# Qwiic_PHT_Sensor_-_MS8607.net
KiCad netlist of a schematic drawn in EAGLE
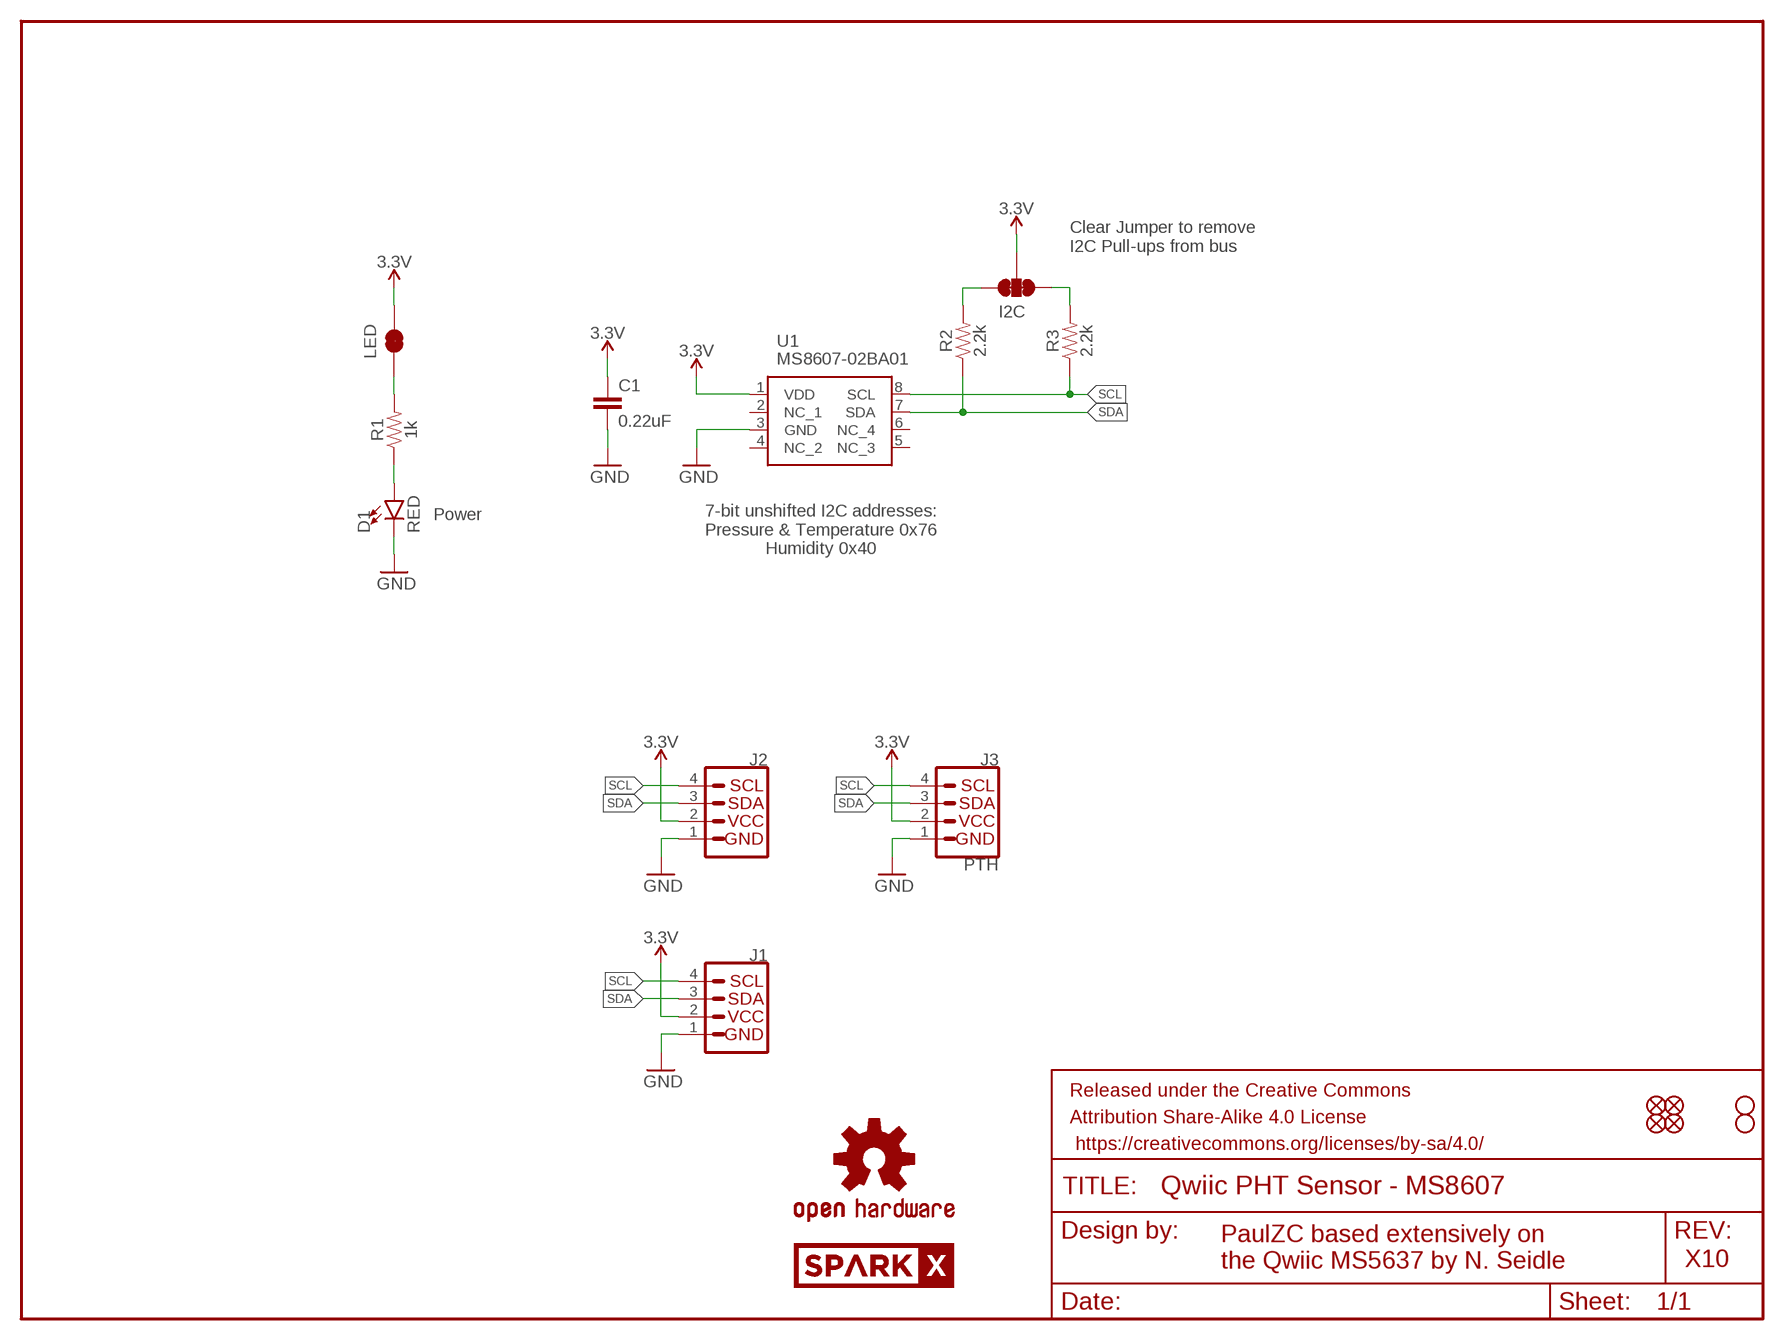
[diagram p0: schematic, sheet 1]

(export (version "E")
  (design (tool "Eeschema 10.0.6"))
  (components
    (comp (ref "C1")
      (value "0.22uF")
      (footprint "eagle-import:0603")
      (libsource (lib "eagle-import") (part "0.22UF-0603-25V-10%"))
    )
    (comp (ref "D1")
      (value "RED")
      (footprint "eagle-import:LED-0603")
      (libsource (lib "eagle-import") (part "LED-RED0603"))
    )
    (comp (ref "FRAME1")
      (value "FRAME-LETTER")
      (footprint "eagle-import:CREATIVE_COMMONS")
      (libsource (lib "eagle-import") (part "FRAME-LETTER"))
    )
    (comp (ref "I2C")
      (value "JUMPER-SMT_3_2-NC_TRACE_SILK")
      (footprint "eagle-import:SMT-JUMPER_3_2-NC_TRACE_SILK")
      (libsource (lib "eagle-import") (part "JUMPER-SMT_3_2-NC_TRACE_SILK"))
    )
    (comp (ref "J1")
      (value "I2C_STANDARDQWIIC")
      (footprint "eagle-import:1X04_1MM_RA")
      (libsource (lib "eagle-import") (part "I2C_STANDARDQWIIC"))
    )
    (comp (ref "J2")
      (value "I2C_STANDARDQWIIC")
      (footprint "eagle-import:1X04_1MM_RA")
      (libsource (lib "eagle-import") (part "I2C_STANDARDQWIIC"))
    )
    (comp (ref "J3")
      (value "PTH")
      (footprint "eagle-import:1X04_NO_SILK")
      (libsource (lib "eagle-import") (part "SparkX_I2C_STANDARD_NO_SILK"))
    )
    (comp (ref "JP1")
      (value "FIDUCIALUFIDUCIAL")
      (footprint "eagle-import:MICRO-FIDUCIAL")
      (libsource (lib "eagle-import") (part "FIDUCIALUFIDUCIAL"))
    )
    (comp (ref "JP2")
      (value "FIDUCIALUFIDUCIAL")
      (footprint "eagle-import:MICRO-FIDUCIAL")
      (libsource (lib "eagle-import") (part "FIDUCIALUFIDUCIAL"))
    )
    (comp (ref "JP3")
      (value "STAND-OFF")
      (footprint "eagle-import:STAND-OFF")
      (libsource (lib "eagle-import") (part "STAND-OFF"))
    )
    (comp (ref "JP4")
      (value "STAND-OFF")
      (footprint "eagle-import:STAND-OFF")
      (libsource (lib "eagle-import") (part "STAND-OFF"))
    )
    (comp (ref "JP5")
      (value "FIDUCIALUFIDUCIAL")
      (footprint "eagle-import:MICRO-FIDUCIAL")
      (libsource (lib "eagle-import") (part "FIDUCIALUFIDUCIAL"))
    )
    (comp (ref "JP6")
      (value "FIDUCIALUFIDUCIAL")
      (footprint "eagle-import:MICRO-FIDUCIAL")
      (libsource (lib "eagle-import") (part "FIDUCIALUFIDUCIAL"))
    )
    (comp (ref "LED")
      (value "JUMPER-SMT_2_NC_TRACE_SILK")
      (footprint "eagle-import:SMT-JUMPER_2_NC_TRACE_SILK")
      (libsource (lib "eagle-import") (part "JUMPER-SMT_2_NC_TRACE_SILK"))
    )
    (comp (ref "LOGO1")
      (value "OSHW-LOGOMINI")
      (footprint "eagle-import:OSHW-LOGO-MINI")
      (libsource (lib "eagle-import") (part "OSHW-LOGOMINI"))
    )
    (comp (ref "R1")
      (value "1k")
      (footprint "eagle-import:0603")
      (libsource (lib "eagle-import") (part "1KOHM-0603-1/10W-1%"))
    )
    (comp (ref "R2")
      (value "2.2k")
      (footprint "eagle-import:0603")
      (libsource (lib "eagle-import") (part "2.2KOHM-0603-1/10W-1%"))
    )
    (comp (ref "R3")
      (value "2.2k")
      (footprint "eagle-import:0603")
      (libsource (lib "eagle-import") (part "2.2KOHM-0603-1/10W-1%"))
    )
    (comp (ref "U$1")
      (value "SPARKX-LOGO4")
      (footprint "eagle-import:SPARKX-MEDIUM")
      (libsource (lib "eagle-import") (part "SPARKX-LOGO4"))
    )
    (comp (ref "U$2")
      (value "SPARKX-LOGO4")
      (footprint "eagle-import:SPARKX-MEDIUM")
      (libsource (lib "eagle-import") (part "SPARKX-LOGO4"))
    )
    (comp (ref "U1")
      (value "MS8607-02BA01")
      (footprint "eagle-import:MS8607-02BA01")
      (libsource (lib "eagle-import") (part "MS8607-02BA01"))
    )
  )
  (nets
    (net (code "1") (name "3.3V") (class "Default")
      (node (ref "C1") (pin "1") (pinfunction "1_1") (pintype "passive"))
      (node (ref "I2C") (pin "2") (pinfunction "2_2") (pintype "passive"))
      (node (ref "J1") (pin "2") (pinfunction "2_2") (pintype "power_in"))
      (node (ref "J2") (pin "2") (pinfunction "2_2") (pintype "power_in"))
      (node (ref "J3") (pin "2") (pinfunction "VCC_2") (pintype "power_in"))
      (node (ref "LED") (pin "2") (pinfunction "2_2") (pintype "passive"))
      (node (ref "U1") (pin "1") (pinfunction "VDD_1") (pintype "power_in"))
    )
    (net (code "2") (name "GND") (class "Default")
      (node (ref "C1") (pin "2") (pinfunction "2_2") (pintype "passive"))
      (node (ref "D1") (pin "C") (pinfunction "C_C") (pintype "passive"))
      (node (ref "J1") (pin "1") (pinfunction "1_1") (pintype "power_in"))
      (node (ref "J2") (pin "1") (pinfunction "1_1") (pintype "power_in"))
      (node (ref "J3") (pin "1") (pinfunction "GND_1") (pintype "power_in"))
      (node (ref "U1") (pin "3") (pinfunction "GND_3") (pintype "power_in"))
    )
    (net (code "3") (name "Net-(D1-PadA)") (class "Default")
      (node (ref "D1") (pin "A") (pinfunction "A_A") (pintype "passive"))
      (node (ref "R1") (pin "1") (pinfunction "1_1") (pintype "passive"))
    )
    (net (code "4") (name "Net-(I2C-Pad1)") (class "Default")
      (node (ref "I2C") (pin "1") (pinfunction "1_1") (pintype "passive"))
      (node (ref "R3") (pin "2") (pinfunction "2_2") (pintype "passive"))
    )
    (net (code "5") (name "Net-(I2C-Pad3)") (class "Default")
      (node (ref "I2C") (pin "3") (pinfunction "3_3") (pintype "passive"))
      (node (ref "R2") (pin "2") (pinfunction "2_2") (pintype "passive"))
    )
    (net (code "6") (name "Net-(LED-Pad1)") (class "Default")
      (node (ref "LED") (pin "1") (pinfunction "1_1") (pintype "passive"))
      (node (ref "R1") (pin "2") (pinfunction "2_2") (pintype "passive"))
    )
    (net (code "7") (name "SCL") (class "Default")
      (node (ref "J1") (pin "4") (pinfunction "4_4") (pintype "passive"))
      (node (ref "J2") (pin "4") (pinfunction "4_4") (pintype "passive"))
      (node (ref "J3") (pin "4") (pinfunction "SCL_4") (pintype "passive"))
      (node (ref "R3") (pin "1") (pinfunction "1_1") (pintype "passive"))
      (node (ref "U1") (pin "8") (pinfunction "SCL_8") (pintype "bidirectional"))
    )
    (net (code "8") (name "SDA") (class "Default")
      (node (ref "J1") (pin "3") (pinfunction "3_3") (pintype "passive"))
      (node (ref "J2") (pin "3") (pinfunction "3_3") (pintype "passive"))
      (node (ref "J3") (pin "3") (pinfunction "SDA_3") (pintype "passive"))
      (node (ref "R2") (pin "1") (pinfunction "1_1") (pintype "passive"))
      (node (ref "U1") (pin "7") (pinfunction "SDA_7") (pintype "bidirectional"))
    )
    (net (code "9") (name "unconnected-(U1-NC_1-Pad2)") (class "Default")
      (node (ref "U1") (pin "2") (pinfunction "NC_1_2") (pintype "no_connect"))
    )
    (net (code "10") (name "unconnected-(U1-NC_2-Pad4)") (class "Default")
      (node (ref "U1") (pin "4") (pinfunction "NC_2_4") (pintype "no_connect"))
    )
    (net (code "11") (name "unconnected-(U1-NC_3-Pad5)") (class "Default")
      (node (ref "U1") (pin "5") (pinfunction "NC_3_5") (pintype "no_connect"))
    )
    (net (code "12") (name "unconnected-(U1-NC_4-Pad6)") (class "Default")
      (node (ref "U1") (pin "6") (pinfunction "NC_4_6") (pintype "no_connect"))
    )
  )
)
